# BG1094_TopLevel.net
KiCad netlist of a schematic drawn in Altium Designer
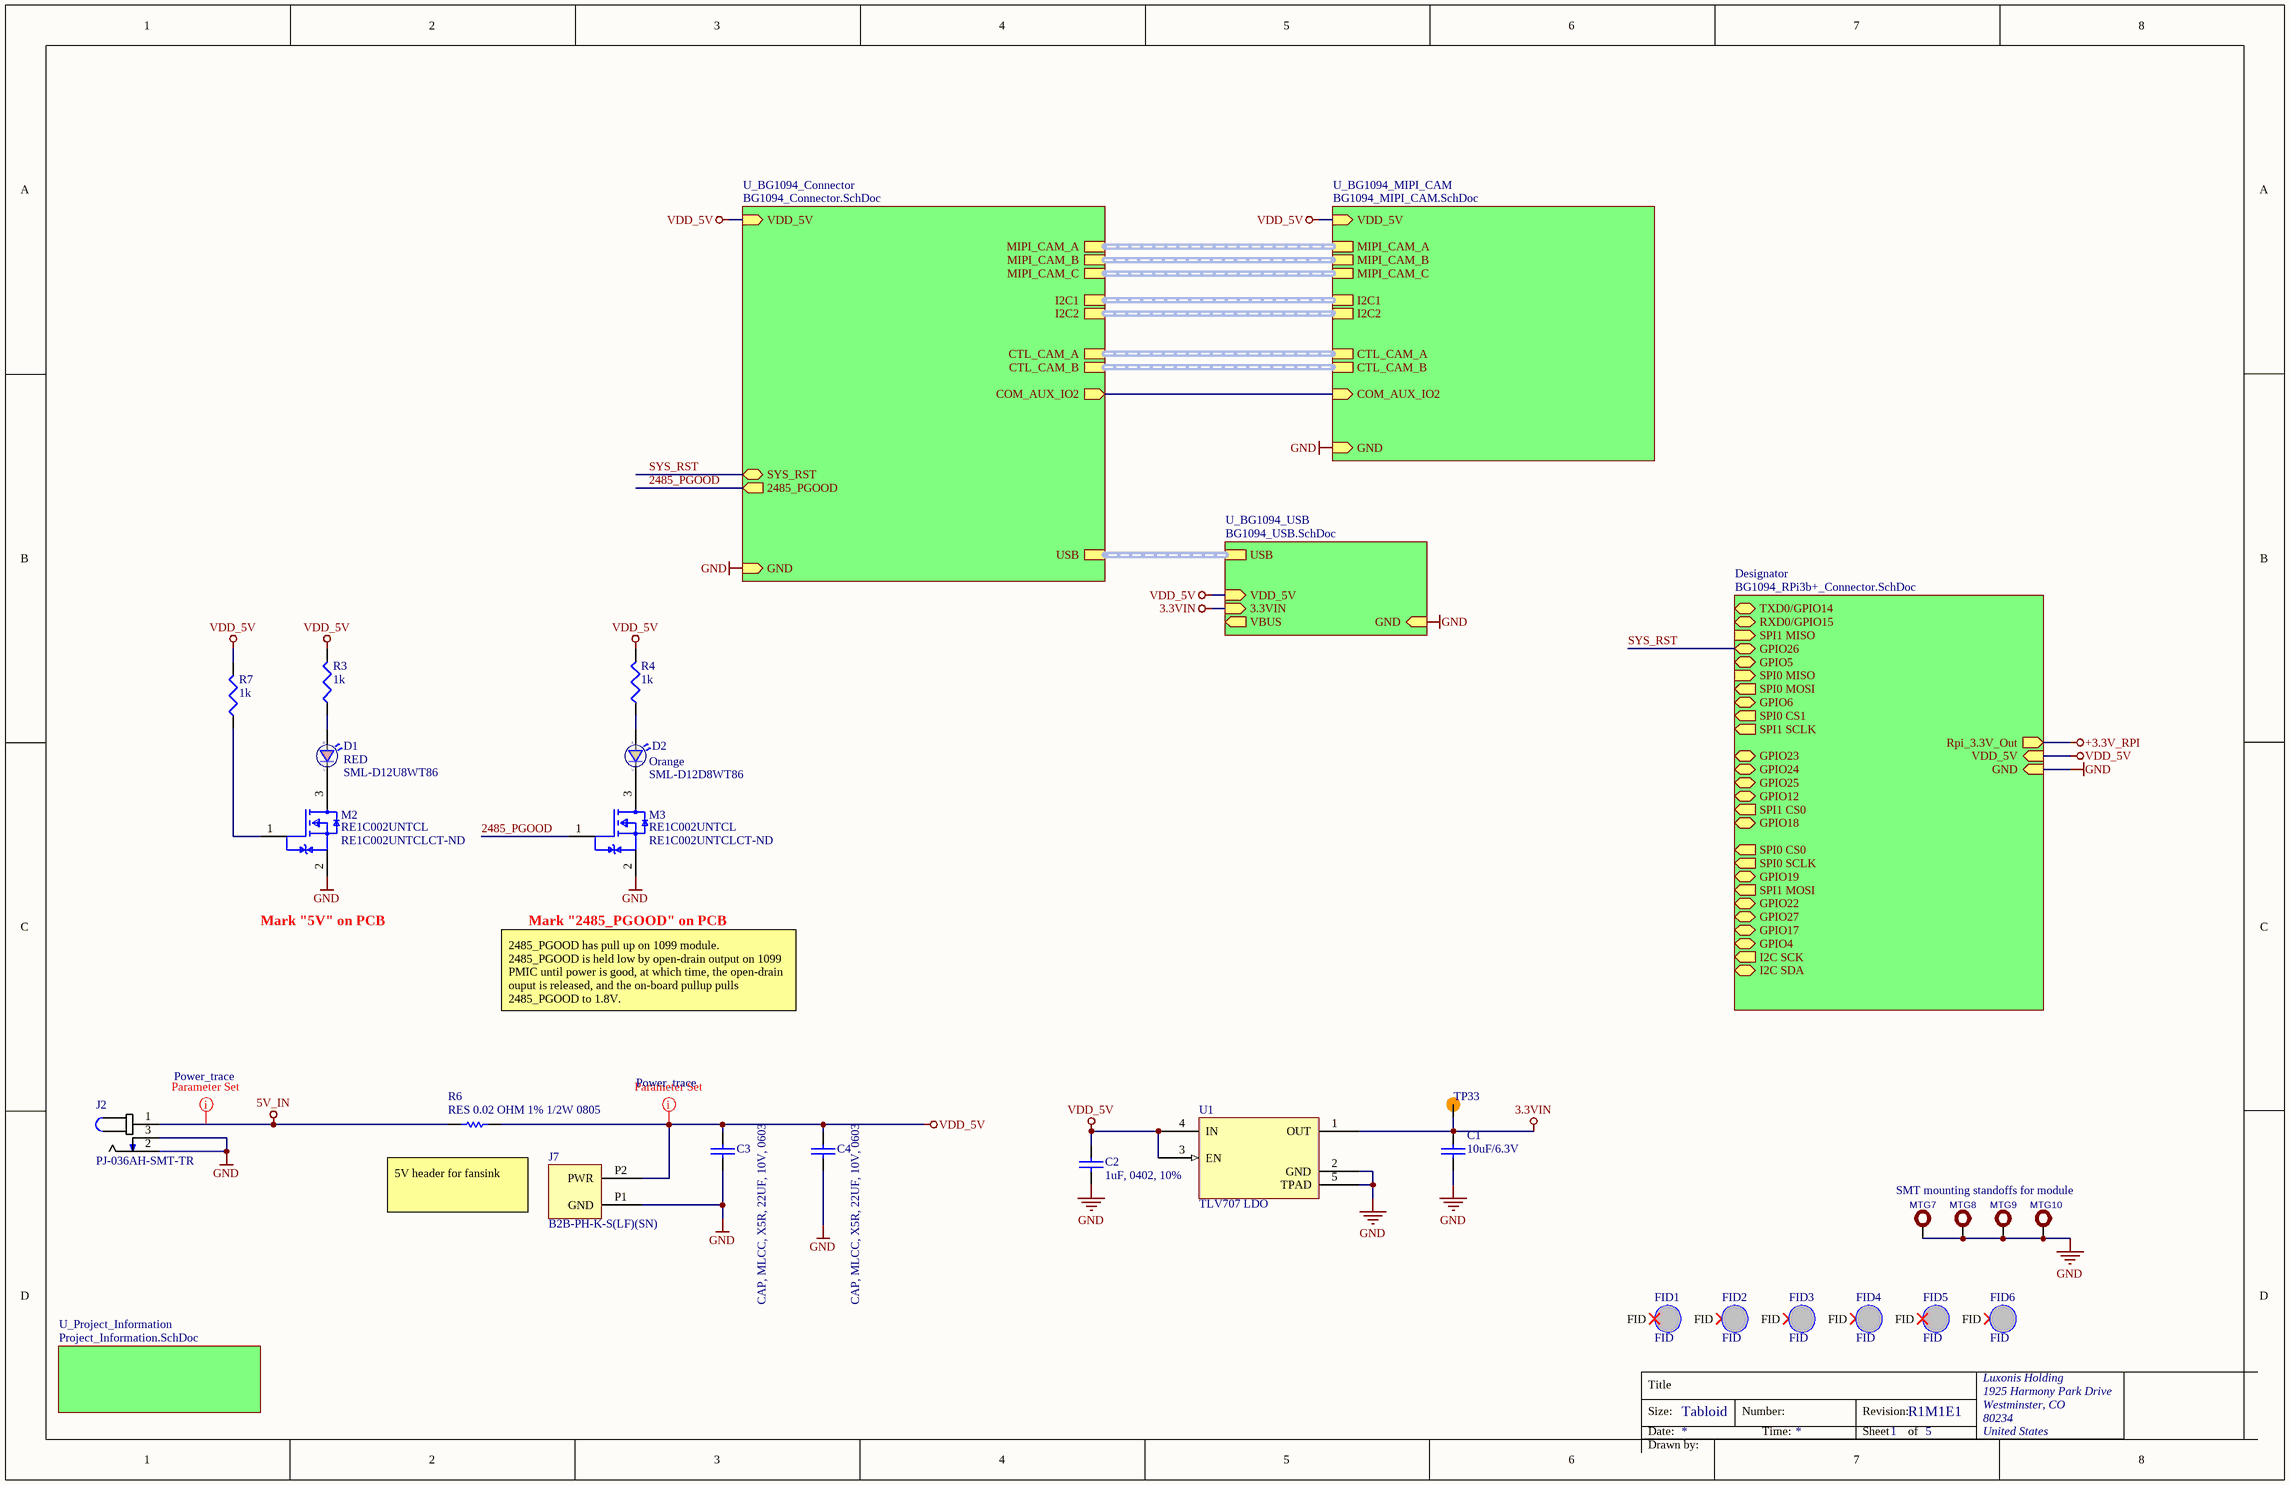
[diagram p0: BG1094_TopLevel.SchDoc]

(export (version "E")
  (design (tool "Eeschema 10.0.6"))
  (components
    (comp (ref "C1")
      (value "10uF/6.3V")
      (footprint "CAPC0402(1005)70_N")
      (description "SMD Multilayer Ceramic Capacitor, 0402 [1005 Metric], 10 µF, 6.3 V, ± 20%, X5R")
      (libsource (lib "MV0235_R4M0E0") (part "CAP"))
    )
    (comp (ref "C2")
      (value "1uF, 0402, 10%")
      (footprint "IPC_RES_CAP:CAPC0402(1005)70_N")
      (description "Cap Ceramic 1uF 10V X5R 10% SMD 0402 85C Paper T/R")
      (fields
        (field (name "MANUFACTURER") "Samsung")
        (field (name "MANUFACTURER PART NUMBER") "CL05A105KP5NNNC")
      )
      (libsource (lib "Schlib1") (part "CL05A105KP5NNNC"))
    )
    (comp (ref "C3")
      (value "CAP, MLCC, X5R, 22UF, 10V, 0603")
      (footprint "IPC_RES_CAP:CAPC0603(1608)100_N")
      (libsource (lib "Schlib1") (part "GRM188R61A226ME15D"))
    )
    (comp (ref "C4")
      (value "CAP, MLCC, X5R, 22UF, 10V, 0603")
      (footprint "IPC_RES_CAP:CAPC0603(1608)100_N")
      (libsource (lib "Schlib1") (part "GRM188R61A226ME15D"))
    )
    (comp (ref "D1")
      (value "RED")
      (footprint "Luxonis:LED_0603")
      (description "LED RED DIFFUSED 0603 SMD")
      (fields (field (name "MANUFACTURER PART NUMBER 1") "SML-D12U8WT86"))
      (libsource (lib "Luxonis") (part "LED_RED_0603"))
    )
    (comp (ref "D2")
      (value "SML-D12D8WT86")
      (footprint "Luxonis:LED_0603")
      (description "LED ORANGE DIFFUSED 0603 SMD")
      (fields (field (name "COLOR") "Orange"))
      (libsource (lib "Luxonis") (part "LED_ORANGE_0603"))
    )
    (comp (ref "FID1")
      (value "FID")
      (footprint "Luxonis:FIDUCIAL_1MM")
      (description "Fiducial mark")
      (libsource (lib "Luxonis") (part "FID"))
    )
    (comp (ref "FID2")
      (value "FID")
      (footprint "Luxonis:FIDUCIAL_1MM")
      (description "Fiducial mark")
      (libsource (lib "Luxonis") (part "FID"))
    )
    (comp (ref "FID3")
      (value "FID")
      (footprint "Luxonis:FIDUCIAL_1MM")
      (description "Fiducial mark")
      (libsource (lib "Luxonis") (part "FID"))
    )
    (comp (ref "FID4")
      (value "FID")
      (footprint "Luxonis:FIDUCIAL_1MM")
      (description "Fiducial mark")
      (libsource (lib "Luxonis") (part "FID"))
    )
    (comp (ref "FID5")
      (value "FID")
      (footprint "Luxonis:FIDUCIAL_1MM")
      (description "Fiducial mark")
      (libsource (lib "Luxonis") (part "FID"))
    )
    (comp (ref "FID6")
      (value "FID")
      (footprint "Luxonis:FIDUCIAL_1MM")
      (description "Fiducial mark")
      (libsource (lib "Luxonis") (part "FID"))
    )
    (comp (ref "J2")
      (value "PJ-036AH-SMT-TR")
      (footprint "Luxonis:CUI_PJ-036AH-SMT-TR")
      (description "2.0 x 6.3 mm, 5.0 A, Horizontal, Surface Mount (SMT), Dc Power Jack Connector")
      (libsource (lib "Luxonis") (part "PJ-036AH-SMT-TR"))
    )
    (comp (ref "J7")
      (value "B2B-PH-K-S(LF)(SN)")
      (footprint "Luxonis:*JST_B2B-PH-K-S(LF)(SN)")
      (description "CONN HEADER VERT 2POS 2MM")
      (fields (field (name "MANUFACTURER") "JST"))
      (libsource (lib "Luxonis") (part "B2B-PH-K-S(LF)(SN)"))
    )
    (comp (ref "M2")
      (value "RE1C002UNTCL")
      (footprint "Luxonis:SOT-416FL")
      (description "MOSFET N-CH 20V 0.2A EMT3")
      (fields (field (name "SUPPLIER PART NUMBER 1") "RE1C002UNTCLCT-ND"))
      (libsource (lib "Luxonis") (part "RE1C002UNTCL"))
    )
    (comp (ref "M3")
      (value "RE1C002UNTCL")
      (footprint "Luxonis:SOT-416FL")
      (description "MOSFET N-CH 20V 0.2A EMT3")
      (fields (field (name "SUPPLIER PART NUMBER 1") "RE1C002UNTCLCT-ND"))
      (libsource (lib "Luxonis") (part "RE1C002UNTCL"))
    )
    (comp (ref "MTG7")
      (value "MTG-HOLE")
      (footprint "RS-CONN:STANDOFF_M2X0.4_3MM")
      (description "Mounting Hole")
      (libsource (lib "RS-CONN") (part "MTG-HOLE_B"))
    )
    (comp (ref "MTG8")
      (value "MTG-HOLE")
      (footprint "RS-CONN:STANDOFF_M2X0.4_3MM")
      (description "Mounting Hole")
      (libsource (lib "RS-CONN") (part "MTG-HOLE_B"))
    )
    (comp (ref "MTG9")
      (value "MTG-HOLE")
      (footprint "RS-CONN:STANDOFF_M2X0.4_3MM")
      (description "Mounting Hole")
      (libsource (lib "RS-CONN") (part "MTG-HOLE_B"))
    )
    (comp (ref "MTG10")
      (value "MTG-HOLE")
      (footprint "RS-CONN:STANDOFF_M2X0.4_3MM")
      (description "Mounting Hole")
      (libsource (lib "RS-CONN") (part "MTG-HOLE_B"))
    )
    (comp (ref "R3")
      (value "1k")
      (footprint "IPC_RES_CAP:RESC0402(1005)_N")
      (description "SMD Chip Resistor, 1 kohm, 50 V, 0402 [1005 Metric], 62.5 mW, ± 1%")
      (libsource (lib "*") (part "RES1"))
    )
    (comp (ref "R4")
      (value "1k")
      (footprint "IPC_RES_CAP:RESC0402(1005)_N")
      (description "SMD Chip Resistor, 1 kohm, 50 V, 0402 [1005 Metric], 62.5 mW, ± 1%")
      (libsource (lib "*") (part "RES1"))
    )
    (comp (ref "R6")
      (value "RES 0.02 OHM 1% 1/2W 0805")
      (footprint "IPC_RES_CAP:RESC0805(2012)_M")
      (libsource (lib "AltiumDesignLibrary") (part "RES"))
    )
    (comp (ref "R7")
      (value "1k")
      (footprint "IPC_RES_CAP:RESC0402(1005)_N")
      (description "SMD Chip Resistor, 1 kohm, 50 V, 0402 [1005 Metric], 62.5 mW, ± 1%")
      (libsource (lib "*") (part "RES1"))
    )
    (comp (ref "TP33")
      (value "TP_SMD")
      (footprint "TP_0.75MM_SMD_NO-SILK")
      (description "circular pad test point, SMD")
      (libsource (lib "Luxonis") (part "TP_SMD"))
    )
    (comp (ref "U1")
      (value "TLV707 LDO")
      (footprint "Luxonis:DFN65P100X40-4L")
      (description "IC REG LDO 1V 0.2A 4X2SON")
      (fields
        (field (name "MANUFACTURER") "Texas Instruments")
        (field (name "MANUFACTURER PART NUMBER") "TLV70710DQNR")
      )
      (libsource (lib "Schlib1") (part "TLV707"))
    )
  )
  (nets
    (net (code "2") (name "/2485_PGOOD") (class "Default")
      (node (ref "M3") (pin "1") (pinfunction "Gate_1") (pintype "passive"))
    )
    (net (code "39") (name "3.3VIN") (class "Default")
      (node (ref "C1") (pin "2") (pinfunction "2_2") (pintype "passive"))
      (node (ref "TP33") (pin "1") (pintype "passive"))
      (node (ref "U1") (pin "1") (pinfunction "OUT_1") (pintype "power_in"))
    )
    (net (code "40") (name "5V_IN") (class "Default")
      (node (ref "J2") (pin "1") (pinfunction "1_1") (pintype "passive"))
      (node (ref "R6") (pin "2") (pinfunction "2_2") (pintype "passive"))
    )
    (net (code "41") (name "GND") (class "Default")
      (node (ref "C1") (pin "1") (pinfunction "1_1") (pintype "passive"))
      (node (ref "C2") (pin "2") (pinfunction "2_2") (pintype "passive"))
      (node (ref "C3") (pin "2") (pinfunction "2_2") (pintype "passive"))
      (node (ref "C4") (pin "2") (pinfunction "2_2") (pintype "passive"))
      (node (ref "J2") (pin "2") (pinfunction "2_2") (pintype "passive"))
      (node (ref "J2") (pin "3") (pinfunction "3_3") (pintype "passive"))
      (node (ref "J7") (pin "P1") (pinfunction "GND_P1") (pintype "passive"))
      (node (ref "M2") (pin "2") (pinfunction "Source_2") (pintype "passive"))
      (node (ref "M3") (pin "2") (pinfunction "Source_2") (pintype "passive"))
      (node (ref "MTG10") (pin "1") (pintype "passive"))
      (node (ref "MTG7") (pin "1") (pintype "passive"))
      (node (ref "MTG8") (pin "1") (pintype "passive"))
      (node (ref "MTG9") (pin "1") (pintype "passive"))
      (node (ref "U1") (pin "2") (pinfunction "GND_2") (pintype "power_in"))
      (node (ref "U1") (pin "5") (pinfunction "TPAD_5") (pintype "passive"))
    )
    (net (code "42") (name "Net-(D1-A)") (class "Default")
      (node (ref "D1") (pin "2") (pinfunction "A_2") (pintype "passive"))
      (node (ref "R3") (pin "1") (pintype "passive"))
    )
    (net (code "43") (name "Net-(D1-C)") (class "Default")
      (node (ref "D1") (pin "1") (pinfunction "C_1") (pintype "passive"))
      (node (ref "M2") (pin "3") (pinfunction "Drain_3") (pintype "passive"))
    )
    (net (code "44") (name "Net-(D2-A)") (class "Default")
      (node (ref "D2") (pin "2") (pinfunction "A_2") (pintype "passive"))
      (node (ref "R4") (pin "1") (pintype "passive"))
    )
    (net (code "45") (name "Net-(D2-C)") (class "Default")
      (node (ref "D2") (pin "1") (pinfunction "C_1") (pintype "passive"))
      (node (ref "M3") (pin "3") (pinfunction "Drain_3") (pintype "passive"))
    )
    (net (code "46") (name "Net-(M2-Gate)") (class "Default")
      (node (ref "M2") (pin "1") (pinfunction "Gate_1") (pintype "passive"))
      (node (ref "R7") (pin "1") (pintype "passive"))
    )
    (net (code "47") (name "VDD_5V") (class "Default")
      (node (ref "C2") (pin "1") (pinfunction "1_1") (pintype "passive"))
      (node (ref "C3") (pin "1") (pinfunction "1_1") (pintype "passive"))
      (node (ref "C4") (pin "1") (pinfunction "1_1") (pintype "passive"))
      (node (ref "J7") (pin "P2") (pinfunction "PWR_P2") (pintype "passive"))
      (node (ref "R3") (pin "2") (pintype "passive"))
      (node (ref "R4") (pin "2") (pintype "passive"))
      (node (ref "R6") (pin "1") (pinfunction "1_1") (pintype "passive"))
      (node (ref "R7") (pin "2") (pintype "passive"))
      (node (ref "U1") (pin "3") (pinfunction "EN_3") (pintype "input"))
      (node (ref "U1") (pin "4") (pinfunction "IN_4") (pintype "power_in"))
    )
    (net (code "48") (name "unconnected-(FID1-PadFID)") (class "Default")
      (node (ref "FID1") (pin "FID") (pinfunction "FID_FID") (pintype "input+no_connect"))
    )
    (net (code "49") (name "unconnected-(FID2-PadFID)") (class "Default")
      (node (ref "FID2") (pin "FID") (pinfunction "FID_FID") (pintype "input+no_connect"))
    )
    (net (code "50") (name "unconnected-(FID3-PadFID)") (class "Default")
      (node (ref "FID3") (pin "FID") (pinfunction "FID_FID") (pintype "input+no_connect"))
    )
    (net (code "51") (name "unconnected-(FID4-PadFID)") (class "Default")
      (node (ref "FID4") (pin "FID") (pinfunction "FID_FID") (pintype "input+no_connect"))
    )
    (net (code "52") (name "unconnected-(FID5-PadFID)") (class "Default")
      (node (ref "FID5") (pin "FID") (pinfunction "FID_FID") (pintype "input+no_connect"))
    )
    (net (code "53") (name "unconnected-(FID6-PadFID)") (class "Default")
      (node (ref "FID6") (pin "FID") (pinfunction "FID_FID") (pintype "input+no_connect"))
    )
  )
)
